# BMSv6_BatLength.net
KiCad netlist of a schematic drawn in EAGLE
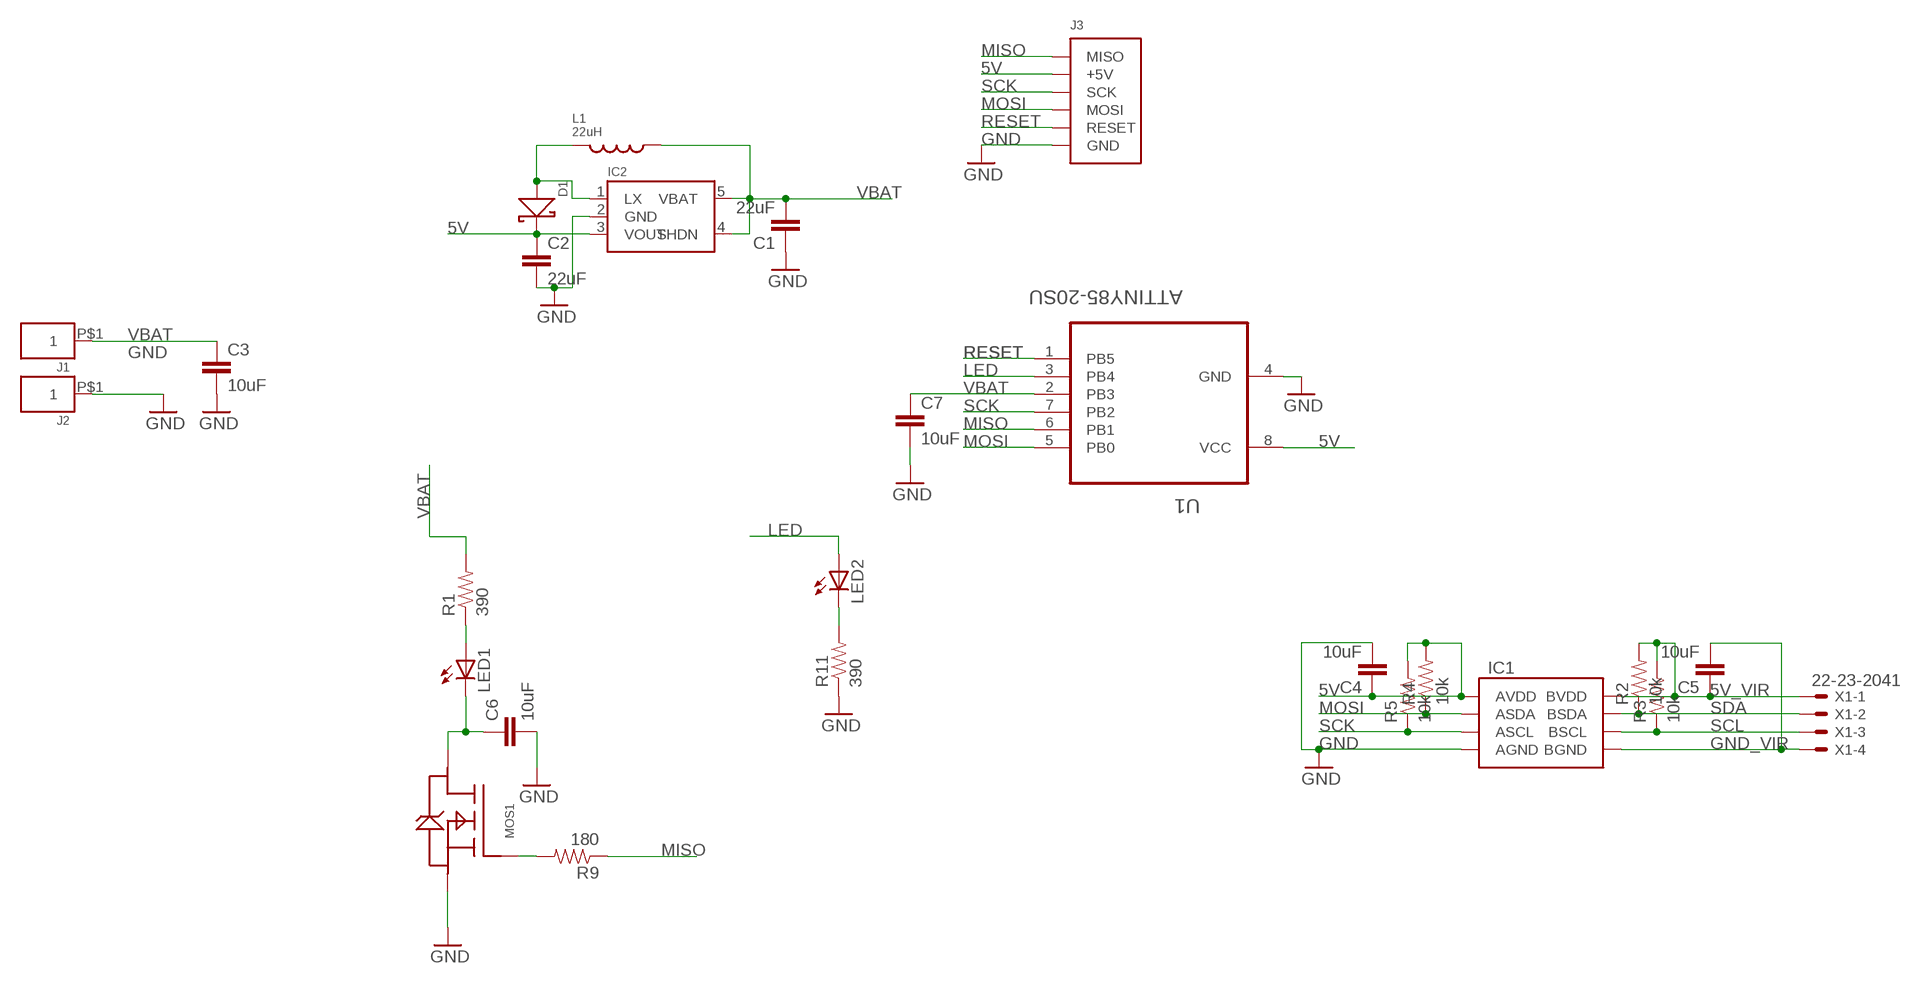
[diagram p0: schematic, sheet 1]

(export (version "E")
  (design (tool "Eeschema 10.0.6"))
  (components
    (comp (ref "C1")
      (value "22uF")
      (footprint "eagle-import:0805-CAP")
      (libsource (lib "eagle-import") (part "10UF10V10%(0805)"))
    )
    (comp (ref "C2")
      (value "22uF")
      (footprint "eagle-import:0805-CAP")
      (libsource (lib "eagle-import") (part "10UF10V10%(0805)"))
    )
    (comp (ref "C3")
      (value "10uF")
      (footprint "eagle-import:0805-CAP")
      (libsource (lib "eagle-import") (part "10UF10V10%(0805)"))
    )
    (comp (ref "C4")
      (value "10uF")
      (footprint "eagle-import:0805-CAP")
      (libsource (lib "eagle-import") (part "10UF10V10%(0805)"))
    )
    (comp (ref "C5")
      (value "10uF")
      (footprint "eagle-import:0805-CAP")
      (libsource (lib "eagle-import") (part "10UF10V10%(0805)"))
    )
    (comp (ref "C6")
      (value "10uF")
      (footprint "eagle-import:0805-CAP")
      (libsource (lib "eagle-import") (part "10UF10V10%(0805)"))
    )
    (comp (ref "C7")
      (value "10uF")
      (footprint "eagle-import:0805-CAP")
      (libsource (lib "eagle-import") (part "10UF10V10%(0805)"))
    )
    (comp (ref "D1")
      (value "DIODE_SCHOTTKYSOD-123")
      (footprint "eagle-import:SOD-123")
      (libsource (lib "eagle-import") (part "DIODE_SCHOTTKYSOD-123"))
    )
    (comp (ref "IC1")
      (value "SI8600_DUALCHANNELISO")
      (footprint "eagle-import:SOIC-8")
      (libsource (lib "eagle-import") (part "SI8600_DUALCHANNELISO"))
    )
    (comp (ref "IC2")
      (value "SP6641")
      (footprint "eagle-import:SOT-23")
      (libsource (lib "eagle-import") (part "SP6641"))
    )
    (comp (ref "J1")
      (value "CONNECTOR_1PIN")
      (footprint "eagle-import:SMD_PAD_.15X.25")
      (libsource (lib "eagle-import") (part "CONNECTOR_1PIN"))
    )
    (comp (ref "J2")
      (value "CONNECTOR_1PIN")
      (footprint "eagle-import:SMD_PAD_.15X.25")
      (libsource (lib "eagle-import") (part "CONNECTOR_1PIN"))
    )
    (comp (ref "J3")
      (value "ISPHEADER")
      (footprint "eagle-import:2X3PIN_.1'")
      (libsource (lib "eagle-import") (part "ISPHEADER"))
    )
    (comp (ref "L1")
      (value "22uH")
      (footprint "eagle-import:6X6MM_IND")
      (libsource (lib "eagle-import") (part "CHIP_IND1"))
    )
    (comp (ref "LED1")
      (value "LEDCHIPLED_0805")
      (footprint "eagle-import:CHIPLED_0805")
      (libsource (lib "eagle-import") (part "LEDCHIPLED_0805"))
    )
    (comp (ref "LED2")
      (value "LEDCHIPLED_0805")
      (footprint "eagle-import:CHIPLED_0805")
      (libsource (lib "eagle-import") (part "LEDCHIPLED_0805"))
    )
    (comp (ref "MOS1")
      (value "MOS_N_LOGIC_PSMN7R0")
      (footprint "eagle-import:LFPAK")
      (libsource (lib "eagle-import") (part "MOS_N_LOGIC_PSMN7R0"))
    )
    (comp (ref "R1")
      (value "390")
      (footprint "eagle-import:0805")
      (libsource (lib "eagle-import") (part "0.3OHM-1/8W-1%(0805)"))
    )
    (comp (ref "R2")
      (value "10k")
      (footprint "eagle-import:0805")
      (libsource (lib "eagle-import") (part "0.3OHM-1/8W-1%(0805)"))
    )
    (comp (ref "R3")
      (value "10k")
      (footprint "eagle-import:0805")
      (libsource (lib "eagle-import") (part "0.3OHM-1/8W-1%(0805)"))
    )
    (comp (ref "R4")
      (value "10k")
      (footprint "eagle-import:0805")
      (libsource (lib "eagle-import") (part "0.3OHM-1/8W-1%(0805)"))
    )
    (comp (ref "R5")
      (value "10k")
      (footprint "eagle-import:0805")
      (libsource (lib "eagle-import") (part "0.3OHM-1/8W-1%(0805)"))
    )
    (comp (ref "R9")
      (value "180")
      (footprint "eagle-import:0805")
      (libsource (lib "eagle-import") (part "0.3OHM-1/8W-1%(0805)"))
    )
    (comp (ref "R11")
      (value "390")
      (footprint "eagle-import:0805")
      (libsource (lib "eagle-import") (part "0.3OHM-1/8W-1%(0805)"))
    )
    (comp (ref "U1")
      (value "ATTINY85-20SU")
      (footprint "eagle-import:SOIC127P798X216-8N")
      (libsource (lib "eagle-import") (part "ATTINY85-20SU"))
    )
    (comp (ref "X1")
      (value "22-23-2041")
      (footprint "eagle-import:22-23-2041")
      (fields (field (name "MF") "MOLEX"))
      (libsource (lib "eagle-import") (part "22-23-2041"))
    )
  )
  (nets
    (net (code "1") (name "5V") (class "Default")
      (node (ref "C2") (pin "1") (pinfunction "1_1") (pintype "passive"))
      (node (ref "C4") (pin "1") (pinfunction "1_1") (pintype "passive"))
      (node (ref "D1") (pin "CATHODE") (pinfunction "CATHODE_CATHODE") (pintype "bidirectional"))
      (node (ref "IC1") (pin "P$1") (pinfunction "AVDD_P$1") (pintype "bidirectional"))
      (node (ref "IC2") (pin "3") (pinfunction "VOUT_3") (pintype "bidirectional"))
      (node (ref "J3") (pin "P$2") (pinfunction "+5V_P$2") (pintype "bidirectional"))
      (node (ref "R4") (pin "2") (pinfunction "2_2") (pintype "passive"))
      (node (ref "R5") (pin "2") (pinfunction "2_2") (pintype "passive"))
      (node (ref "U1") (pin "8") (pinfunction "VCC_8") (pintype "power_in"))
    )
    (net (code "2") (name "5V_VIR") (class "Default")
      (node (ref "C5") (pin "1") (pinfunction "1_1") (pintype "passive"))
      (node (ref "IC1") (pin "P$8") (pinfunction "BVDD_P$8") (pintype "bidirectional"))
      (node (ref "R2") (pin "2") (pinfunction "2_2") (pintype "passive"))
      (node (ref "R3") (pin "2") (pinfunction "2_2") (pintype "passive"))
      (node (ref "X1") (pin "1") (pinfunction "S_1") (pintype "passive"))
    )
    (net (code "3") (name "GND") (class "Default")
      (node (ref "C1") (pin "1") (pinfunction "1_1") (pintype "passive"))
      (node (ref "C2") (pin "2") (pinfunction "2_2") (pintype "passive"))
      (node (ref "C3") (pin "2") (pinfunction "2_2") (pintype "passive"))
      (node (ref "C4") (pin "2") (pinfunction "2_2") (pintype "passive"))
      (node (ref "C6") (pin "2") (pinfunction "2_2") (pintype "passive"))
      (node (ref "C7") (pin "2") (pinfunction "2_2") (pintype "passive"))
      (node (ref "IC1") (pin "P$4") (pinfunction "AGND_P$4") (pintype "bidirectional"))
      (node (ref "IC2") (pin "2") (pinfunction "GND_2") (pintype "bidirectional"))
      (node (ref "J2") (pin "P$1") (pinfunction "1_P$1") (pintype "bidirectional"))
      (node (ref "J3") (pin "P$6") (pinfunction "GND_P$6") (pintype "bidirectional"))
      (node (ref "MOS1") (pin "P$1") (pinfunction "SOURCE_P$1") (pintype "bidirectional"))
      (node (ref "MOS1") (pin "P$2") (pinfunction "SOURCE_P$2") (pintype "bidirectional"))
      (node (ref "MOS1") (pin "P$3") (pinfunction "SOURCE_P$3") (pintype "bidirectional"))
      (node (ref "R11") (pin "1") (pinfunction "1_1") (pintype "passive"))
      (node (ref "U1") (pin "4") (pinfunction "GND_4") (pintype "passive"))
    )
    (net (code "4") (name "GND_VIR") (class "Default")
      (node (ref "C5") (pin "2") (pinfunction "2_2") (pintype "passive"))
      (node (ref "IC1") (pin "P$5") (pinfunction "BGND_P$5") (pintype "bidirectional"))
      (node (ref "X1") (pin "4") (pinfunction "S_4") (pintype "passive"))
    )
    (net (code "5") (name "LED") (class "Default")
      (node (ref "LED2") (pin "A") (pinfunction "A_A") (pintype "passive"))
      (node (ref "U1") (pin "3") (pinfunction "PB4_3") (pintype "bidirectional"))
    )
    (net (code "6") (name "MISO") (class "Default")
      (node (ref "J3") (pin "P$1") (pinfunction "MISO_P$1") (pintype "bidirectional"))
      (node (ref "R9") (pin "1") (pinfunction "1_1") (pintype "passive"))
      (node (ref "U1") (pin "6") (pinfunction "PB1_6") (pintype "bidirectional"))
    )
    (net (code "7") (name "MOSI") (class "Default")
      (node (ref "IC1") (pin "P$2") (pinfunction "ASDA_P$2") (pintype "bidirectional"))
      (node (ref "J3") (pin "P$4") (pinfunction "MOSI_P$4") (pintype "bidirectional"))
      (node (ref "R4") (pin "1") (pinfunction "1_1") (pintype "passive"))
      (node (ref "U1") (pin "5") (pinfunction "PB0_5") (pintype "bidirectional"))
    )
    (net (code "8") (name "Net-(IC2-LX)") (class "Default")
      (node (ref "D1") (pin "ANODE") (pinfunction "ANODE_ANODE") (pintype "bidirectional"))
      (node (ref "IC2") (pin "1") (pinfunction "LX_1") (pintype "bidirectional"))
      (node (ref "L1") (pin "P$1") (pinfunction "P$1_P$1") (pintype "bidirectional"))
    )
    (net (code "9") (name "Net-(LED1-PadA)") (class "Default")
      (node (ref "LED1") (pin "A") (pinfunction "A_A") (pintype "passive"))
      (node (ref "R1") (pin "1") (pinfunction "1_1") (pintype "passive"))
    )
    (net (code "10") (name "Net-(LED2-PadC)") (class "Default")
      (node (ref "LED2") (pin "C") (pinfunction "C_C") (pintype "passive"))
      (node (ref "R11") (pin "2") (pinfunction "2_2") (pintype "passive"))
    )
    (net (code "11") (name "Net-(MOS1-DRAIN)") (class "Default")
      (node (ref "C6") (pin "1") (pinfunction "1_1") (pintype "passive"))
      (node (ref "LED1") (pin "C") (pinfunction "C_C") (pintype "passive"))
      (node (ref "MOS1") (pin "P$5") (pinfunction "DRAIN_P$5") (pintype "bidirectional"))
    )
    (net (code "12") (name "Net-(MOS1-GATE)") (class "Default")
      (node (ref "MOS1") (pin "P$4") (pinfunction "GATE_P$4") (pintype "bidirectional"))
      (node (ref "R9") (pin "2") (pinfunction "2_2") (pintype "passive"))
    )
    (net (code "13") (name "RESET") (class "Default")
      (node (ref "J3") (pin "P$5") (pinfunction "RESET_P$5") (pintype "bidirectional"))
      (node (ref "U1") (pin "1") (pinfunction "PB5_1") (pintype "bidirectional"))
    )
    (net (code "14") (name "SCK") (class "Default")
      (node (ref "IC1") (pin "P$3") (pinfunction "ASCL_P$3") (pintype "bidirectional"))
      (node (ref "J3") (pin "P$3") (pinfunction "SCK_P$3") (pintype "bidirectional"))
      (node (ref "R5") (pin "1") (pinfunction "1_1") (pintype "passive"))
      (node (ref "U1") (pin "7") (pinfunction "PB2_7") (pintype "bidirectional"))
    )
    (net (code "15") (name "SCL") (class "Default")
      (node (ref "IC1") (pin "P$6") (pinfunction "BSCL_P$6") (pintype "bidirectional"))
      (node (ref "R3") (pin "1") (pinfunction "1_1") (pintype "passive"))
      (node (ref "X1") (pin "3") (pinfunction "S_3") (pintype "passive"))
    )
    (net (code "16") (name "SDA") (class "Default")
      (node (ref "IC1") (pin "P$7") (pinfunction "BSDA_P$7") (pintype "bidirectional"))
      (node (ref "R2") (pin "1") (pinfunction "1_1") (pintype "passive"))
      (node (ref "X1") (pin "2") (pinfunction "S_2") (pintype "passive"))
    )
    (net (code "17") (name "VBAT") (class "Default")
      (node (ref "C1") (pin "2") (pinfunction "2_2") (pintype "passive"))
      (node (ref "C3") (pin "1") (pinfunction "1_1") (pintype "passive"))
      (node (ref "C7") (pin "1") (pinfunction "1_1") (pintype "passive"))
      (node (ref "IC2") (pin "4") (pinfunction "SHDN_4") (pintype "bidirectional"))
      (node (ref "IC2") (pin "5") (pinfunction "VBAT_5") (pintype "bidirectional"))
      (node (ref "J1") (pin "P$1") (pinfunction "1_P$1") (pintype "bidirectional"))
      (node (ref "L1") (pin "P$2") (pinfunction "P$2_P$2") (pintype "bidirectional"))
      (node (ref "R1") (pin "2") (pinfunction "2_2") (pintype "passive"))
      (node (ref "U1") (pin "2") (pinfunction "PB3_2") (pintype "bidirectional"))
    )
  )
)
